# rhoby_motor.net
KiCad netlist of a schematic drawn in EAGLE
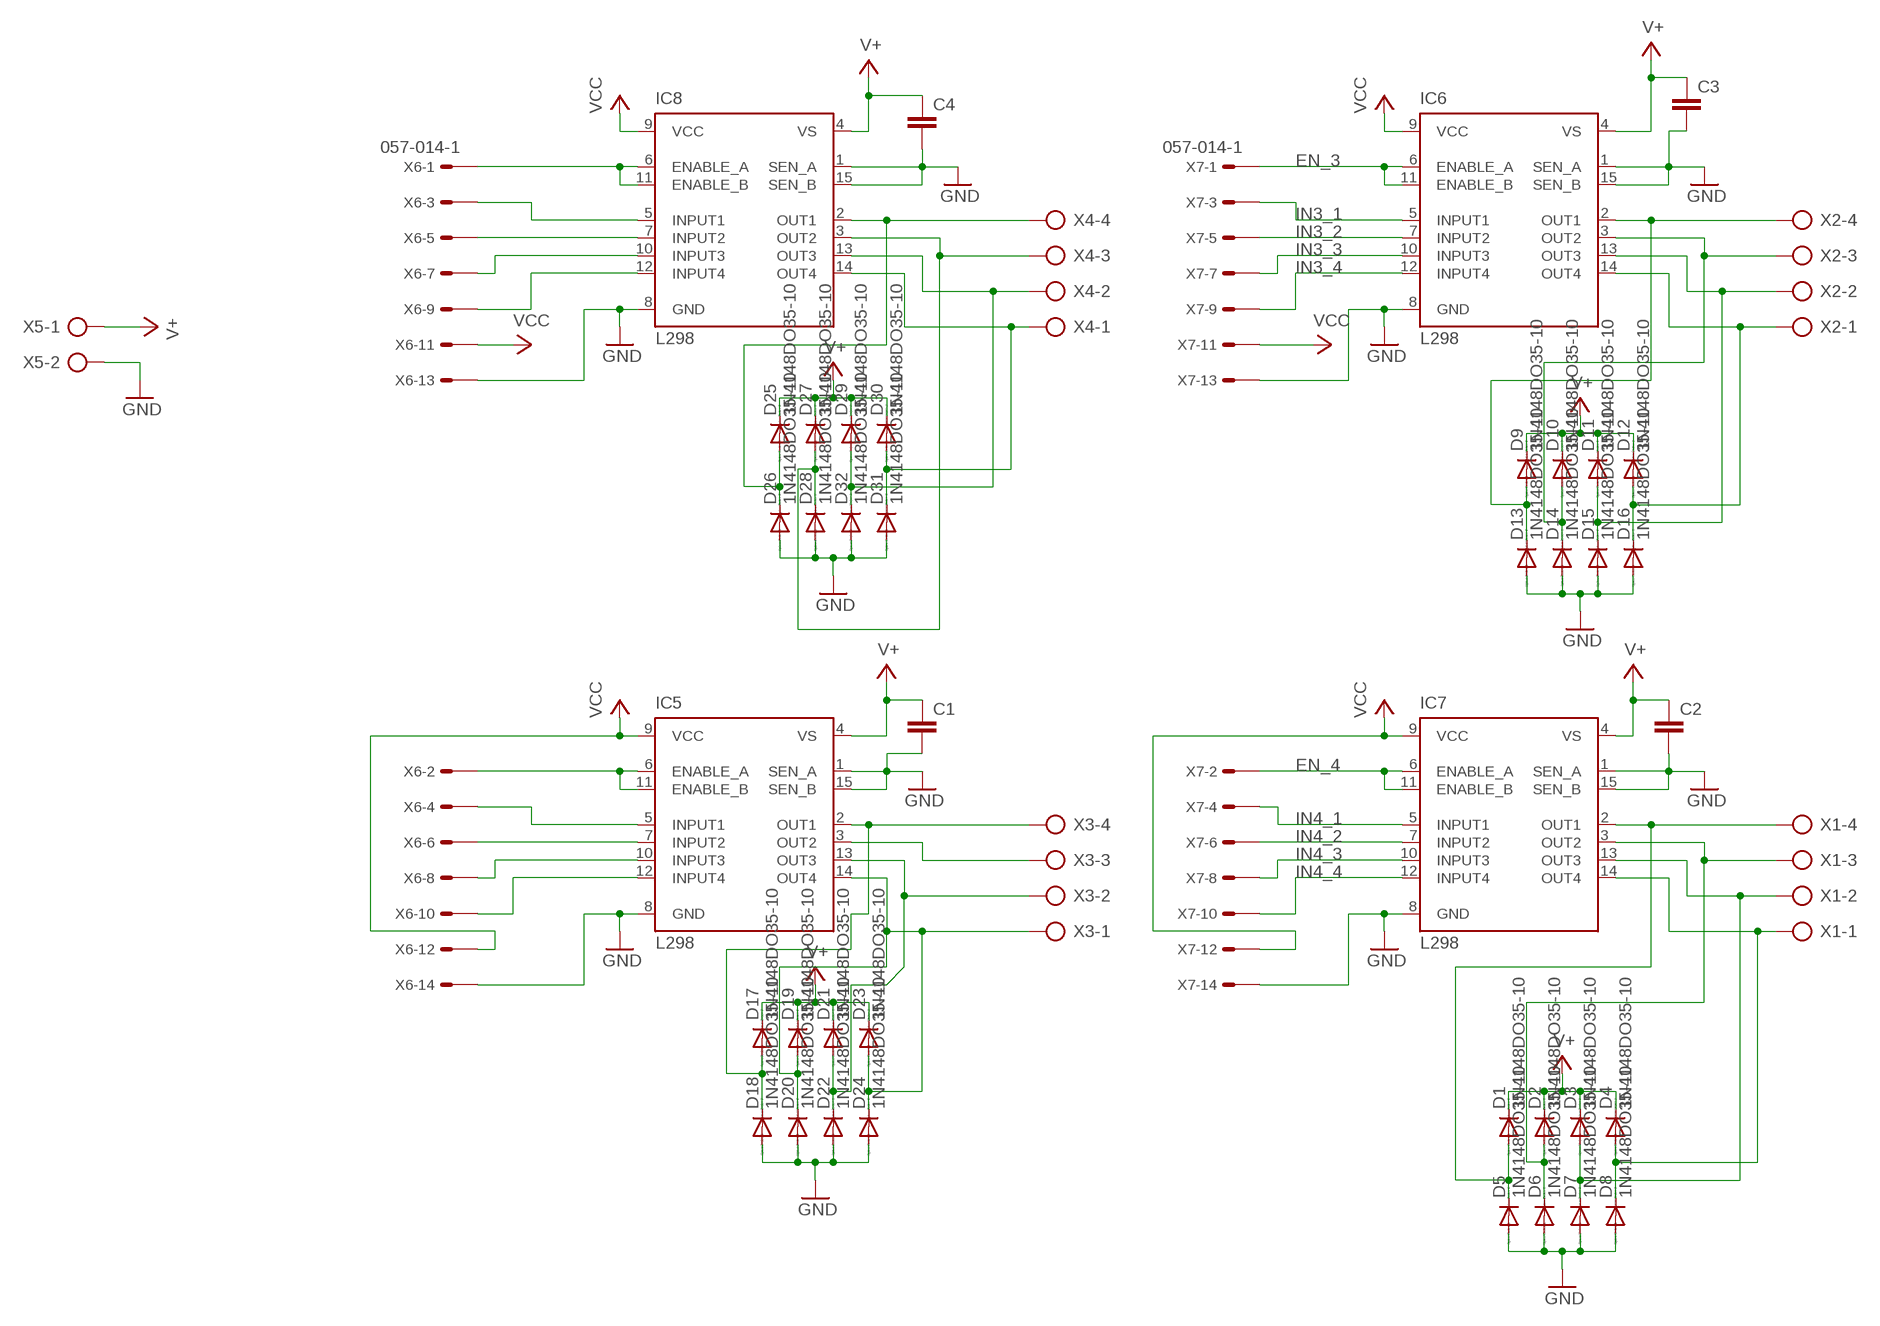
[diagram p0: schematic, sheet 1]

(export (version "E")
  (design (tool "Eeschema 10.0.6"))
  (components
    (comp (ref "C1")
      (value "C-EUC1210")
      (footprint "eagle-import:C1210")
      (libsource (lib "eagle-import") (part "C-EUC1210"))
    )
    (comp (ref "C2")
      (value "C-EUC1210")
      (footprint "eagle-import:C1210")
      (libsource (lib "eagle-import") (part "C-EUC1210"))
    )
    (comp (ref "C3")
      (value "C-EUC1210")
      (footprint "eagle-import:C1210")
      (libsource (lib "eagle-import") (part "C-EUC1210"))
    )
    (comp (ref "C4")
      (value "C-EUC1210")
      (footprint "eagle-import:C1210")
      (libsource (lib "eagle-import") (part "C-EUC1210"))
    )
    (comp (ref "D1")
      (value "1N4148DO35-10")
      (footprint "eagle-import:DO35-10")
      (libsource (lib "eagle-import") (part "1N4148DO35-10"))
    )
    (comp (ref "D2")
      (value "1N4148DO35-10")
      (footprint "eagle-import:DO35-10")
      (libsource (lib "eagle-import") (part "1N4148DO35-10"))
    )
    (comp (ref "D3")
      (value "1N4148DO35-10")
      (footprint "eagle-import:DO35-10")
      (libsource (lib "eagle-import") (part "1N4148DO35-10"))
    )
    (comp (ref "D4")
      (value "1N4148DO35-10")
      (footprint "eagle-import:DO35-10")
      (libsource (lib "eagle-import") (part "1N4148DO35-10"))
    )
    (comp (ref "D5")
      (value "1N4148DO35-10")
      (footprint "eagle-import:DO35-10")
      (libsource (lib "eagle-import") (part "1N4148DO35-10"))
    )
    (comp (ref "D6")
      (value "1N4148DO35-10")
      (footprint "eagle-import:DO35-10")
      (libsource (lib "eagle-import") (part "1N4148DO35-10"))
    )
    (comp (ref "D7")
      (value "1N4148DO35-10")
      (footprint "eagle-import:DO35-10")
      (libsource (lib "eagle-import") (part "1N4148DO35-10"))
    )
    (comp (ref "D8")
      (value "1N4148DO35-10")
      (footprint "eagle-import:DO35-10")
      (libsource (lib "eagle-import") (part "1N4148DO35-10"))
    )
    (comp (ref "D9")
      (value "1N4148DO35-10")
      (footprint "eagle-import:DO35-10")
      (libsource (lib "eagle-import") (part "1N4148DO35-10"))
    )
    (comp (ref "D10")
      (value "1N4148DO35-10")
      (footprint "eagle-import:DO35-10")
      (libsource (lib "eagle-import") (part "1N4148DO35-10"))
    )
    (comp (ref "D11")
      (value "1N4148DO35-10")
      (footprint "eagle-import:DO35-10")
      (libsource (lib "eagle-import") (part "1N4148DO35-10"))
    )
    (comp (ref "D12")
      (value "1N4148DO35-10")
      (footprint "eagle-import:DO35-10")
      (libsource (lib "eagle-import") (part "1N4148DO35-10"))
    )
    (comp (ref "D13")
      (value "1N4148DO35-10")
      (footprint "eagle-import:DO35-10")
      (libsource (lib "eagle-import") (part "1N4148DO35-10"))
    )
    (comp (ref "D14")
      (value "1N4148DO35-10")
      (footprint "eagle-import:DO35-10")
      (libsource (lib "eagle-import") (part "1N4148DO35-10"))
    )
    (comp (ref "D15")
      (value "1N4148DO35-10")
      (footprint "eagle-import:DO35-10")
      (libsource (lib "eagle-import") (part "1N4148DO35-10"))
    )
    (comp (ref "D16")
      (value "1N4148DO35-10")
      (footprint "eagle-import:DO35-10")
      (libsource (lib "eagle-import") (part "1N4148DO35-10"))
    )
    (comp (ref "D17")
      (value "1N4148DO35-10")
      (footprint "eagle-import:DO35-10")
      (libsource (lib "eagle-import") (part "1N4148DO35-10"))
    )
    (comp (ref "D18")
      (value "1N4148DO35-10")
      (footprint "eagle-import:DO35-10")
      (libsource (lib "eagle-import") (part "1N4148DO35-10"))
    )
    (comp (ref "D19")
      (value "1N4148DO35-10")
      (footprint "eagle-import:DO35-10")
      (libsource (lib "eagle-import") (part "1N4148DO35-10"))
    )
    (comp (ref "D20")
      (value "1N4148DO35-10")
      (footprint "eagle-import:DO35-10")
      (libsource (lib "eagle-import") (part "1N4148DO35-10"))
    )
    (comp (ref "D21")
      (value "1N4148DO35-10")
      (footprint "eagle-import:DO35-10")
      (libsource (lib "eagle-import") (part "1N4148DO35-10"))
    )
    (comp (ref "D22")
      (value "1N4148DO35-10")
      (footprint "eagle-import:DO35-10")
      (libsource (lib "eagle-import") (part "1N4148DO35-10"))
    )
    (comp (ref "D23")
      (value "1N4148DO35-10")
      (footprint "eagle-import:DO35-10")
      (libsource (lib "eagle-import") (part "1N4148DO35-10"))
    )
    (comp (ref "D24")
      (value "1N4148DO35-10")
      (footprint "eagle-import:DO35-10")
      (libsource (lib "eagle-import") (part "1N4148DO35-10"))
    )
    (comp (ref "D25")
      (value "1N4148DO35-10")
      (footprint "eagle-import:DO35-10")
      (libsource (lib "eagle-import") (part "1N4148DO35-10"))
    )
    (comp (ref "D26")
      (value "1N4148DO35-10")
      (footprint "eagle-import:DO35-10")
      (libsource (lib "eagle-import") (part "1N4148DO35-10"))
    )
    (comp (ref "D27")
      (value "1N4148DO35-10")
      (footprint "eagle-import:DO35-10")
      (libsource (lib "eagle-import") (part "1N4148DO35-10"))
    )
    (comp (ref "D28")
      (value "1N4148DO35-10")
      (footprint "eagle-import:DO35-10")
      (libsource (lib "eagle-import") (part "1N4148DO35-10"))
    )
    (comp (ref "D29")
      (value "1N4148DO35-10")
      (footprint "eagle-import:DO35-10")
      (libsource (lib "eagle-import") (part "1N4148DO35-10"))
    )
    (comp (ref "D30")
      (value "1N4148DO35-10")
      (footprint "eagle-import:DO35-10")
      (libsource (lib "eagle-import") (part "1N4148DO35-10"))
    )
    (comp (ref "D31")
      (value "1N4148DO35-10")
      (footprint "eagle-import:DO35-10")
      (libsource (lib "eagle-import") (part "1N4148DO35-10"))
    )
    (comp (ref "D32")
      (value "1N4148DO35-10")
      (footprint "eagle-import:DO35-10")
      (libsource (lib "eagle-import") (part "1N4148DO35-10"))
    )
    (comp (ref "IC5")
      (value "L298")
      (footprint "eagle-import:MULTIWATT-15")
      (fields (field (name "MPN") "L298N"))
      (libsource (lib "eagle-import") (part "L298"))
    )
    (comp (ref "IC6")
      (value "L298")
      (footprint "eagle-import:MULTIWATT-15")
      (fields (field (name "MPN") "L298N"))
      (libsource (lib "eagle-import") (part "L298"))
    )
    (comp (ref "IC7")
      (value "L298")
      (footprint "eagle-import:MULTIWATT-15")
      (fields (field (name "MPN") "L298N"))
      (libsource (lib "eagle-import") (part "L298"))
    )
    (comp (ref "IC8")
      (value "L298")
      (footprint "eagle-import:MULTIWATT-15")
      (fields (field (name "MPN") "L298N"))
      (libsource (lib "eagle-import") (part "L298"))
    )
    (comp (ref "X1")
      (value "AK500/4")
      (footprint "eagle-import:AK500_4")
      (libsource (lib "eagle-import") (part "AK500/4"))
    )
    (comp (ref "X2")
      (value "AK500/4")
      (footprint "eagle-import:AK500_4")
      (libsource (lib "eagle-import") (part "AK500/4"))
    )
    (comp (ref "X3")
      (value "AK500/4")
      (footprint "eagle-import:AK500_4")
      (libsource (lib "eagle-import") (part "AK500/4"))
    )
    (comp (ref "X4")
      (value "AK500/4")
      (footprint "eagle-import:AK500_4")
      (libsource (lib "eagle-import") (part "AK500/4"))
    )
    (comp (ref "X5")
      (value "AK500/2")
      (footprint "eagle-import:AK500_2")
      (libsource (lib "eagle-import") (part "AK500/2"))
    )
    (comp (ref "X6")
      (value "057-014-1")
      (footprint "eagle-import:057-014-1")
      (libsource (lib "eagle-import") (part "057-014-1"))
    )
    (comp (ref "X7")
      (value "057-014-1")
      (footprint "eagle-import:057-014-1")
      (libsource (lib "eagle-import") (part "057-014-1"))
    )
  )
  (nets
    (net (code "1") (name "/EN_3") (class "Default")
      (node (ref "IC6") (pin "11") (pinfunction "ENABLE_B_11") (pintype "input"))
      (node (ref "IC6") (pin "6") (pinfunction "ENABLE_A_6") (pintype "input"))
      (node (ref "X7") (pin "1") (pinfunction "S_1") (pintype "passive"))
    )
    (net (code "2") (name "/EN_4") (class "Default")
      (node (ref "IC7") (pin "11") (pinfunction "ENABLE_B_11") (pintype "input"))
      (node (ref "IC7") (pin "6") (pinfunction "ENABLE_A_6") (pintype "input"))
      (node (ref "X7") (pin "2") (pinfunction "S_2") (pintype "passive"))
    )
    (net (code "3") (name "/IN3_1") (class "Default")
      (node (ref "IC6") (pin "5") (pinfunction "INPUT1_5") (pintype "input"))
      (node (ref "X7") (pin "3") (pinfunction "S_3") (pintype "passive"))
    )
    (net (code "4") (name "/IN3_2") (class "Default")
      (node (ref "IC6") (pin "7") (pinfunction "INPUT2_7") (pintype "input"))
      (node (ref "X7") (pin "5") (pinfunction "S_5") (pintype "passive"))
    )
    (net (code "5") (name "/IN3_3") (class "Default")
      (node (ref "IC6") (pin "10") (pinfunction "INPUT3_10") (pintype "input"))
      (node (ref "X7") (pin "7") (pinfunction "S_7") (pintype "passive"))
    )
    (net (code "6") (name "/IN3_4") (class "Default")
      (node (ref "IC6") (pin "12") (pinfunction "INPUT4_12") (pintype "input"))
      (node (ref "X7") (pin "9") (pinfunction "S_9") (pintype "passive"))
    )
    (net (code "7") (name "/IN4_1") (class "Default")
      (node (ref "IC7") (pin "5") (pinfunction "INPUT1_5") (pintype "input"))
      (node (ref "X7") (pin "4") (pinfunction "S_4") (pintype "passive"))
    )
    (net (code "8") (name "/IN4_2") (class "Default")
      (node (ref "IC7") (pin "7") (pinfunction "INPUT2_7") (pintype "input"))
      (node (ref "X7") (pin "6") (pinfunction "S_6") (pintype "passive"))
    )
    (net (code "9") (name "/IN4_3") (class "Default")
      (node (ref "IC7") (pin "10") (pinfunction "INPUT3_10") (pintype "input"))
      (node (ref "X7") (pin "8") (pinfunction "S_8") (pintype "passive"))
    )
    (net (code "10") (name "/IN4_4") (class "Default")
      (node (ref "IC7") (pin "12") (pinfunction "INPUT4_12") (pintype "input"))
      (node (ref "X7") (pin "10") (pinfunction "S_10") (pintype "passive"))
    )
    (net (code "11") (name "GND") (class "Default")
      (node (ref "C1") (pin "2") (pinfunction "2_2") (pintype "passive"))
      (node (ref "C2") (pin "2") (pinfunction "2_2") (pintype "passive"))
      (node (ref "C3") (pin "2") (pinfunction "2_2") (pintype "passive"))
      (node (ref "C4") (pin "2") (pinfunction "2_2") (pintype "passive"))
      (node (ref "D13") (pin "A") (pinfunction "A_A") (pintype "passive"))
      (node (ref "D14") (pin "A") (pinfunction "A_A") (pintype "passive"))
      (node (ref "D15") (pin "A") (pinfunction "A_A") (pintype "passive"))
      (node (ref "D16") (pin "A") (pinfunction "A_A") (pintype "passive"))
      (node (ref "D18") (pin "A") (pinfunction "A_A") (pintype "passive"))
      (node (ref "D20") (pin "A") (pinfunction "A_A") (pintype "passive"))
      (node (ref "D22") (pin "A") (pinfunction "A_A") (pintype "passive"))
      (node (ref "D24") (pin "A") (pinfunction "A_A") (pintype "passive"))
      (node (ref "D26") (pin "A") (pinfunction "A_A") (pintype "passive"))
      (node (ref "D28") (pin "A") (pinfunction "A_A") (pintype "passive"))
      (node (ref "D31") (pin "A") (pinfunction "A_A") (pintype "passive"))
      (node (ref "D32") (pin "A") (pinfunction "A_A") (pintype "passive"))
      (node (ref "D5") (pin "A") (pinfunction "A_A") (pintype "passive"))
      (node (ref "D6") (pin "A") (pinfunction "A_A") (pintype "passive"))
      (node (ref "D7") (pin "A") (pinfunction "A_A") (pintype "passive"))
      (node (ref "D8") (pin "A") (pinfunction "A_A") (pintype "passive"))
      (node (ref "IC5") (pin "1") (pinfunction "SEN_A_1") (pintype "input"))
      (node (ref "IC5") (pin "15") (pinfunction "SEN_B_15") (pintype "input"))
      (node (ref "IC5") (pin "8") (pinfunction "GND_8") (pintype "power_in"))
      (node (ref "IC6") (pin "1") (pinfunction "SEN_A_1") (pintype "input"))
      (node (ref "IC6") (pin "15") (pinfunction "SEN_B_15") (pintype "input"))
      (node (ref "IC6") (pin "8") (pinfunction "GND_8") (pintype "power_in"))
      (node (ref "IC7") (pin "1") (pinfunction "SEN_A_1") (pintype "input"))
      (node (ref "IC7") (pin "15") (pinfunction "SEN_B_15") (pintype "input"))
      (node (ref "IC7") (pin "8") (pinfunction "GND_8") (pintype "power_in"))
      (node (ref "IC8") (pin "1") (pinfunction "SEN_A_1") (pintype "input"))
      (node (ref "IC8") (pin "15") (pinfunction "SEN_B_15") (pintype "input"))
      (node (ref "IC8") (pin "8") (pinfunction "GND_8") (pintype "power_in"))
      (node (ref "X5") (pin "2") (pinfunction "KL_2") (pintype "passive"))
      (node (ref "X6") (pin "13") (pinfunction "S_13") (pintype "passive"))
      (node (ref "X6") (pin "14") (pinfunction "S_14") (pintype "passive"))
      (node (ref "X7") (pin "13") (pinfunction "S_13") (pintype "passive"))
      (node (ref "X7") (pin "14") (pinfunction "S_14") (pintype "passive"))
    )
    (net (code "12") (name "Net-(IC5-ENABLE_A)") (class "Default")
      (node (ref "IC5") (pin "11") (pinfunction "ENABLE_B_11") (pintype "input"))
      (node (ref "IC5") (pin "6") (pinfunction "ENABLE_A_6") (pintype "input"))
      (node (ref "X6") (pin "2") (pinfunction "S_2") (pintype "passive"))
    )
    (net (code "13") (name "Net-(IC5-INPUT1)") (class "Default")
      (node (ref "IC5") (pin "5") (pinfunction "INPUT1_5") (pintype "input"))
      (node (ref "X6") (pin "4") (pinfunction "S_4") (pintype "passive"))
    )
    (net (code "14") (name "Net-(IC5-INPUT2)") (class "Default")
      (node (ref "IC5") (pin "7") (pinfunction "INPUT2_7") (pintype "input"))
      (node (ref "X6") (pin "6") (pinfunction "S_6") (pintype "passive"))
    )
    (net (code "15") (name "Net-(IC5-INPUT3)") (class "Default")
      (node (ref "IC5") (pin "10") (pinfunction "INPUT3_10") (pintype "input"))
      (node (ref "X6") (pin "8") (pinfunction "S_8") (pintype "passive"))
    )
    (net (code "16") (name "Net-(IC5-INPUT4)") (class "Default")
      (node (ref "IC5") (pin "12") (pinfunction "INPUT4_12") (pintype "input"))
      (node (ref "X6") (pin "10") (pinfunction "S_10") (pintype "passive"))
    )
    (net (code "17") (name "Net-(IC5-OUT1)") (class "Default")
      (node (ref "D17") (pin "A") (pinfunction "A_A") (pintype "passive"))
      (node (ref "D18") (pin "C") (pinfunction "C_C") (pintype "passive"))
      (node (ref "IC5") (pin "2") (pinfunction "OUT1_2") (pintype "output"))
      (node (ref "X3") (pin "4") (pinfunction "KL_4") (pintype "passive"))
    )
    (net (code "18") (name "Net-(IC5-OUT2)") (class "Default")
      (node (ref "IC5") (pin "3") (pinfunction "OUT2_3") (pintype "output"))
      (node (ref "X3") (pin "3") (pinfunction "KL_3") (pintype "passive"))
    )
    (net (code "19") (name "Net-(IC5-OUT3)") (class "Default")
      (node (ref "D21") (pin "A") (pinfunction "A_A") (pintype "passive"))
      (node (ref "D22") (pin "C") (pinfunction "C_C") (pintype "passive"))
      (node (ref "IC5") (pin "13") (pinfunction "OUT3_13") (pintype "output"))
      (node (ref "X3") (pin "2") (pinfunction "KL_2") (pintype "passive"))
    )
    (net (code "20") (name "Net-(IC5-OUT4)") (class "Default")
      (node (ref "D19") (pin "A") (pinfunction "A_A") (pintype "passive"))
      (node (ref "D20") (pin "C") (pinfunction "C_C") (pintype "passive"))
      (node (ref "D23") (pin "A") (pinfunction "A_A") (pintype "passive"))
      (node (ref "D24") (pin "C") (pinfunction "C_C") (pintype "passive"))
      (node (ref "IC5") (pin "14") (pinfunction "OUT4_14") (pintype "output"))
      (node (ref "X3") (pin "1") (pinfunction "KL_1") (pintype "passive"))
    )
    (net (code "21") (name "Net-(IC6-OUT1)") (class "Default")
      (node (ref "D13") (pin "C") (pinfunction "C_C") (pintype "passive"))
      (node (ref "D9") (pin "A") (pinfunction "A_A") (pintype "passive"))
      (node (ref "IC6") (pin "2") (pinfunction "OUT1_2") (pintype "output"))
      (node (ref "X2") (pin "4") (pinfunction "KL_4") (pintype "passive"))
    )
    (net (code "22") (name "Net-(IC6-OUT2)") (class "Default")
      (node (ref "D10") (pin "A") (pinfunction "A_A") (pintype "passive"))
      (node (ref "D14") (pin "C") (pinfunction "C_C") (pintype "passive"))
      (node (ref "IC6") (pin "3") (pinfunction "OUT2_3") (pintype "output"))
      (node (ref "X2") (pin "3") (pinfunction "KL_3") (pintype "passive"))
    )
    (net (code "23") (name "Net-(IC6-OUT3)") (class "Default")
      (node (ref "D11") (pin "A") (pinfunction "A_A") (pintype "passive"))
      (node (ref "D15") (pin "C") (pinfunction "C_C") (pintype "passive"))
      (node (ref "IC6") (pin "13") (pinfunction "OUT3_13") (pintype "output"))
      (node (ref "X2") (pin "2") (pinfunction "KL_2") (pintype "passive"))
    )
    (net (code "24") (name "Net-(IC6-OUT4)") (class "Default")
      (node (ref "D12") (pin "A") (pinfunction "A_A") (pintype "passive"))
      (node (ref "D16") (pin "C") (pinfunction "C_C") (pintype "passive"))
      (node (ref "IC6") (pin "14") (pinfunction "OUT4_14") (pintype "output"))
      (node (ref "X2") (pin "1") (pinfunction "KL_1") (pintype "passive"))
    )
    (net (code "25") (name "Net-(IC7-OUT1)") (class "Default")
      (node (ref "D1") (pin "A") (pinfunction "A_A") (pintype "passive"))
      (node (ref "D5") (pin "C") (pinfunction "C_C") (pintype "passive"))
      (node (ref "IC7") (pin "2") (pinfunction "OUT1_2") (pintype "output"))
      (node (ref "X1") (pin "4") (pinfunction "KL_4") (pintype "passive"))
    )
    (net (code "26") (name "Net-(IC7-OUT2)") (class "Default")
      (node (ref "D2") (pin "A") (pinfunction "A_A") (pintype "passive"))
      (node (ref "D6") (pin "C") (pinfunction "C_C") (pintype "passive"))
      (node (ref "IC7") (pin "3") (pinfunction "OUT2_3") (pintype "output"))
      (node (ref "X1") (pin "3") (pinfunction "KL_3") (pintype "passive"))
    )
    (net (code "27") (name "Net-(IC7-OUT3)") (class "Default")
      (node (ref "D3") (pin "A") (pinfunction "A_A") (pintype "passive"))
      (node (ref "D7") (pin "C") (pinfunction "C_C") (pintype "passive"))
      (node (ref "IC7") (pin "13") (pinfunction "OUT3_13") (pintype "output"))
      (node (ref "X1") (pin "2") (pinfunction "KL_2") (pintype "passive"))
    )
    (net (code "28") (name "Net-(IC7-OUT4)") (class "Default")
      (node (ref "D4") (pin "A") (pinfunction "A_A") (pintype "passive"))
      (node (ref "D8") (pin "C") (pinfunction "C_C") (pintype "passive"))
      (node (ref "IC7") (pin "14") (pinfunction "OUT4_14") (pintype "output"))
      (node (ref "X1") (pin "1") (pinfunction "KL_1") (pintype "passive"))
    )
    (net (code "29") (name "Net-(IC8-ENABLE_A)") (class "Default")
      (node (ref "IC8") (pin "11") (pinfunction "ENABLE_B_11") (pintype "input"))
      (node (ref "IC8") (pin "6") (pinfunction "ENABLE_A_6") (pintype "input"))
      (node (ref "X6") (pin "1") (pinfunction "S_1") (pintype "passive"))
    )
    (net (code "30") (name "Net-(IC8-INPUT1)") (class "Default")
      (node (ref "IC8") (pin "5") (pinfunction "INPUT1_5") (pintype "input"))
      (node (ref "X6") (pin "3") (pinfunction "S_3") (pintype "passive"))
    )
    (net (code "31") (name "Net-(IC8-INPUT2)") (class "Default")
      (node (ref "IC8") (pin "7") (pinfunction "INPUT2_7") (pintype "input"))
      (node (ref "X6") (pin "5") (pinfunction "S_5") (pintype "passive"))
    )
    (net (code "32") (name "Net-(IC8-INPUT3)") (class "Default")
      (node (ref "IC8") (pin "10") (pinfunction "INPUT3_10") (pintype "input"))
      (node (ref "X6") (pin "7") (pinfunction "S_7") (pintype "passive"))
    )
    (net (code "33") (name "Net-(IC8-INPUT4)") (class "Default")
      (node (ref "IC8") (pin "12") (pinfunction "INPUT4_12") (pintype "input"))
      (node (ref "X6") (pin "9") (pinfunction "S_9") (pintype "passive"))
    )
    (net (code "34") (name "Net-(IC8-OUT1)") (class "Default")
      (node (ref "D25") (pin "A") (pinfunction "A_A") (pintype "passive"))
      (node (ref "D26") (pin "C") (pinfunction "C_C") (pintype "passive"))
      (node (ref "IC8") (pin "2") (pinfunction "OUT1_2") (pintype "output"))
      (node (ref "X4") (pin "4") (pinfunction "KL_4") (pintype "passive"))
    )
    (net (code "35") (name "Net-(IC8-OUT2)") (class "Default")
      (node (ref "D27") (pin "A") (pinfunction "A_A") (pintype "passive"))
      (node (ref "D28") (pin "C") (pinfunction "C_C") (pintype "passive"))
      (node (ref "IC8") (pin "3") (pinfunction "OUT2_3") (pintype "output"))
      (node (ref "X4") (pin "3") (pinfunction "KL_3") (pintype "passive"))
    )
    (net (code "36") (name "Net-(IC8-OUT3)") (class "Default")
      (node (ref "D29") (pin "A") (pinfunction "A_A") (pintype "passive"))
      (node (ref "D32") (pin "C") (pinfunction "C_C") (pintype "passive"))
      (node (ref "IC8") (pin "13") (pinfunction "OUT3_13") (pintype "output"))
      (node (ref "X4") (pin "2") (pinfunction "KL_2") (pintype "passive"))
    )
    (net (code "37") (name "Net-(IC8-OUT4)") (class "Default")
      (node (ref "D30") (pin "A") (pinfunction "A_A") (pintype "passive"))
      (node (ref "D31") (pin "C") (pinfunction "C_C") (pintype "passive"))
      (node (ref "IC8") (pin "14") (pinfunction "OUT4_14") (pintype "output"))
      (node (ref "X4") (pin "1") (pinfunction "KL_1") (pintype "passive"))
    )
    (net (code "38") (name "V+") (class "Default")
      (node (ref "C1") (pin "1") (pinfunction "1_1") (pintype "passive"))
      (node (ref "C2") (pin "1") (pinfunction "1_1") (pintype "passive"))
      (node (ref "C3") (pin "1") (pinfunction "1_1") (pintype "passive"))
      (node (ref "C4") (pin "1") (pinfunction "1_1") (pintype "passive"))
      (node (ref "D1") (pin "C") (pinfunction "C_C") (pintype "passive"))
      (node (ref "D10") (pin "C") (pinfunction "C_C") (pintype "passive"))
      (node (ref "D11") (pin "C") (pinfunction "C_C") (pintype "passive"))
      (node (ref "D12") (pin "C") (pinfunction "C_C") (pintype "passive"))
      (node (ref "D17") (pin "C") (pinfunction "C_C") (pintype "passive"))
      (node (ref "D19") (pin "C") (pinfunction "C_C") (pintype "passive"))
      (node (ref "D2") (pin "C") (pinfunction "C_C") (pintype "passive"))
      (node (ref "D21") (pin "C") (pinfunction "C_C") (pintype "passive"))
      (node (ref "D23") (pin "C") (pinfunction "C_C") (pintype "passive"))
      (node (ref "D25") (pin "C") (pinfunction "C_C") (pintype "passive"))
      (node (ref "D27") (pin "C") (pinfunction "C_C") (pintype "passive"))
      (node (ref "D29") (pin "C") (pinfunction "C_C") (pintype "passive"))
      (node (ref "D3") (pin "C") (pinfunction "C_C") (pintype "passive"))
      (node (ref "D30") (pin "C") (pinfunction "C_C") (pintype "passive"))
      (node (ref "D4") (pin "C") (pinfunction "C_C") (pintype "passive"))
      (node (ref "D9") (pin "C") (pinfunction "C_C") (pintype "passive"))
      (node (ref "IC5") (pin "4") (pinfunction "VS_4") (pintype "power_in"))
      (node (ref "IC6") (pin "4") (pinfunction "VS_4") (pintype "power_in"))
      (node (ref "IC7") (pin "4") (pinfunction "VS_4") (pintype "power_in"))
      (node (ref "IC8") (pin "4") (pinfunction "VS_4") (pintype "power_in"))
      (node (ref "X5") (pin "1") (pinfunction "KL_1") (pintype "passive"))
    )
    (net (code "39") (name "VCC") (class "Default")
      (node (ref "IC5") (pin "9") (pinfunction "VCC_9") (pintype "power_in"))
      (node (ref "IC6") (pin "9") (pinfunction "VCC_9") (pintype "power_in"))
      (node (ref "IC7") (pin "9") (pinfunction "VCC_9") (pintype "power_in"))
      (node (ref "IC8") (pin "9") (pinfunction "VCC_9") (pintype "power_in"))
      (node (ref "X6") (pin "11") (pinfunction "S_11") (pintype "passive"))
      (node (ref "X6") (pin "12") (pinfunction "S_12") (pintype "passive"))
      (node (ref "X7") (pin "11") (pinfunction "S_11") (pintype "passive"))
      (node (ref "X7") (pin "12") (pinfunction "S_12") (pintype "passive"))
    )
  )
)
